# PSU.net
KiCad netlist of a schematic drawn in Altium Designer
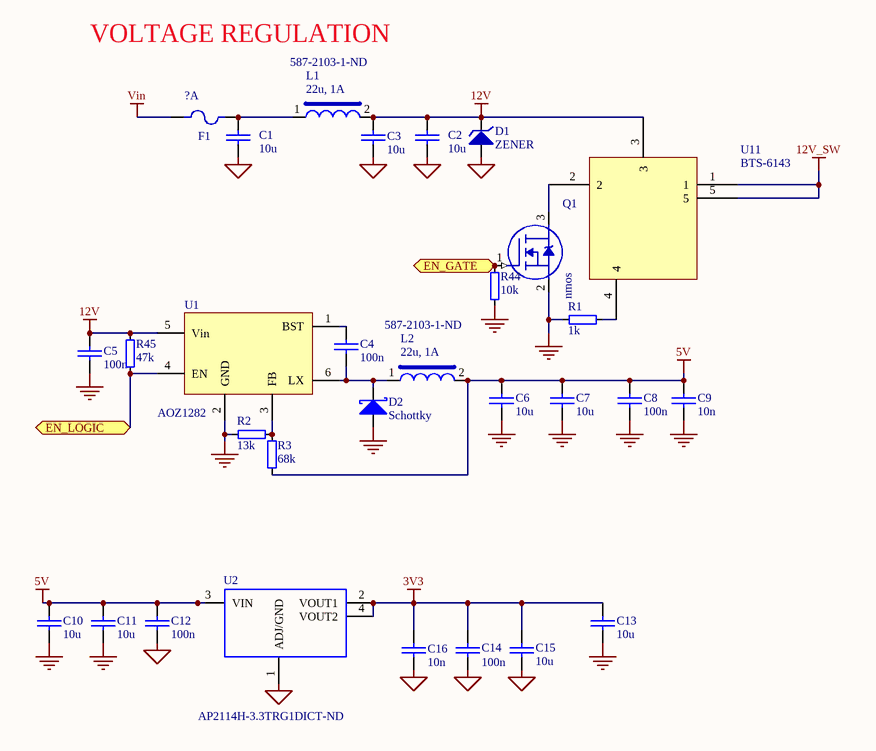
[diagram p0: PSU.SchDoc]

(export (version "E")
  (design (tool "Eeschema 10.0.6"))
  (components
    (comp (ref "C1")
      (value "10u")
      (footprint "0805")
      (description "Capacitor")
      (libsource (lib "Schematic Library") (part "CAPACITOR"))
    )
    (comp (ref "C2")
      (value "10u")
      (footprint "0805")
      (description "Capacitor")
      (libsource (lib "Schematic Library") (part "CAPACITOR"))
    )
    (comp (ref "C3")
      (value "10u")
      (footprint "0805")
      (description "Capacitor")
      (libsource (lib "Schematic Library") (part "CAPACITOR"))
    )
    (comp (ref "C4")
      (value "100n")
      (footprint "0603")
      (fields (field (name "DIGIKEY PART NUMBER") "PCC2153CT-ND"))
      (libsource (lib "*") (part "CAP"))
    )
    (comp (ref "C5")
      (value "100n")
      (footprint "0603")
      (fields (field (name "DIGIKEY PART NUMBER") "PCC2153CT-ND"))
      (libsource (lib "*") (part "CAP"))
    )
    (comp (ref "C6")
      (value "10u")
      (footprint "0805")
      (description "Capacitor")
      (libsource (lib "Schematic Library") (part "CAP"))
    )
    (comp (ref "C7")
      (value "10u")
      (footprint "0805")
      (description "Capacitor")
      (libsource (lib "Schematic Library") (part "CAP"))
    )
    (comp (ref "C8")
      (value "100n")
      (footprint "0603")
      (fields (field (name "DIGIKEY PART NUMBER") "PCC2153CT-ND"))
      (libsource (lib "*") (part "CAP"))
    )
    (comp (ref "C9")
      (value "10n")
      (footprint "0603")
      (fields (field (name "DIGIKEY PART NUMBER") "PCC2153CT-ND"))
      (libsource (lib "*") (part "CAP"))
    )
    (comp (ref "C10")
      (value "10u")
      (footprint "0805")
      (description "Capacitor")
      (libsource (lib "Schematic Library") (part "CAP"))
    )
    (comp (ref "C11")
      (value "10u")
      (footprint "0805")
      (description "Capacitor")
      (libsource (lib "Schematic Library") (part "CAP"))
    )
    (comp (ref "C12")
      (value "100n")
      (footprint "0603")
      (description "Capacitor")
      (libsource (lib "Schematic Library") (part "CAPACITOR"))
    )
    (comp (ref "C13")
      (value "10u")
      (footprint "0805")
      (description "Capacitor")
      (libsource (lib "Schematic Library") (part "CAP"))
    )
    (comp (ref "C14")
      (value "100n")
      (footprint "0603")
      (fields (field (name "DIGIKEY PART NUMBER") "490-4775-1-ND"))
      (libsource (lib "*") (part "CAP"))
    )
    (comp (ref "C15")
      (value "10u")
      (footprint "0805")
      (description "Capacitor")
      (libsource (lib "Schematic Library") (part "CAPACITOR"))
    )
    (comp (ref "C16")
      (value "10n")
      (footprint "0603")
      (fields (field (name "DIGIKEY PART NUMBER") "PCC2153CT-ND"))
      (libsource (lib "*") (part "CAP"))
    )
    (comp (ref "D1")
      (value "ZENER")
      (footprint "DO214AC")
      (description "Zener Diode")
      (libsource (lib "Schematic Library") (part "ZENER"))
    )
    (comp (ref "D2")
      (value "Schottky")
      (footprint "DO214AC")
      (description "Schottky Diode")
      (fields (field (name "DIGIKEY PART NUMBER") "SD103AWSTPMSCT-ND"))
      (libsource (lib "Schematic Library") (part "DIODE SCHOTTKY"))
    )
    (comp (ref "F1")
      (value "?A")
      (footprint "1206")
      (description "Thermal Fuse")
      (libsource (lib "Schematic Library") (part "FUSE"))
    )
    (comp (ref "L1")
      (value "22u, 1A")
      (footprint "2220")
      (description "Standard single coil inductor")
      (fields (field (name "SUPPLIER PART NUMBER 1") "587-2103-1-ND"))
      (libsource (lib "Schematic Library") (part "INDUCTOR-1 COIL"))
    )
    (comp (ref "L2")
      (value "22u, 1A")
      (footprint "2220")
      (description "Standard single coil inductor")
      (fields (field (name "SUPPLIER PART NUMBER 1") "587-2103-1-ND"))
      (libsource (lib "Schematic Library") (part "INDUCTOR-1 COIL"))
    )
    (comp (ref "Q1")
      (value "nmos")
      (footprint "SOT23")
      (description "N-Channel MOSFET")
      (libsource (lib "Schematic Library") (part "MOSFET-N"))
    )
    (comp (ref "R1")
      (value "1k")
      (footprint "0603")
      (description "Resistor")
      (libsource (lib "Schematic Library") (part "RESISTOR"))
    )
    (comp (ref "R2")
      (value "13k")
      (footprint "0603")
      (description "Resistor")
      (libsource (lib "Schematic Library") (part "RESISTOR"))
    )
    (comp (ref "R3")
      (value "68k")
      (footprint "0603")
      (description "Resistor")
      (libsource (lib "Schematic Library") (part "RESISTOR"))
    )
    (comp (ref "R44") (value "10k") (footprint "0603") (libsource (lib "*") (part "RES4")))
    (comp (ref "R45")
      (value "47k")
      (footprint "0805")
      (description "Resistor")
      (libsource (lib "Schematic Library") (part "RESISTOR"))
    )
    (comp (ref "U1")
      (value "AOZ1282")
      (footprint "SOT23-6")
      (fields (field (name "DIGIKEY PART NUMBER") "785-1613-1-ND"))
      (libsource (lib "Schematic Library") (part "AOZ1280"))
    )
    (comp (ref "U2")
      (value "AP2114H-3.3TRG1DICT-ND")
      (footprint "SOT223")
      (libsource (lib "Schematic Library") (part "TLV1117-33"))
    )
    (comp (ref "U11")
      (value "BTS-6143")
      (footprint "TO252-5-11")
      (libsource (lib "zytek_ctl") (part "BTS-6143"))
    )
  )
  (nets
    (net (code "1") (name "/EN_GATE") (class "Default")
      (node (ref "Q1") (pin "1") (pinfunction "G_1") (pintype "input"))
      (node (ref "R44") (pin "1") (pintype "passive"))
    )
    (net (code "2") (name "/EN_LOGIC") (class "Default")
      (node (ref "R45") (pin "2") (pintype "passive"))
      (node (ref "U1") (pin "4") (pinfunction "EN_4") (pintype "passive"))
    )
    (net (code "3") (name "3V3") (class "Default")
      (node (ref "C13") (pin "2") (pinfunction "2_2") (pintype "passive"))
      (node (ref "C14") (pin "1") (pinfunction "1_1") (pintype "passive"))
      (node (ref "C15") (pin "1") (pinfunction "1_1") (pintype "passive"))
      (node (ref "C16") (pin "1") (pinfunction "1_1") (pintype "passive"))
      (node (ref "U2") (pin "2") (pinfunction "VOUT1_2") (pintype "passive"))
      (node (ref "U2") (pin "4") (pinfunction "VOUT2_4") (pintype "passive"))
    )
    (net (code "4") (name "5V") (class "Default")
      (node (ref "C10") (pin "2") (pinfunction "2_2") (pintype "passive"))
      (node (ref "C11") (pin "2") (pinfunction "2_2") (pintype "passive"))
      (node (ref "C12") (pin "1") (pinfunction "1_1") (pintype "passive"))
      (node (ref "C6") (pin "2") (pinfunction "2_2") (pintype "passive"))
      (node (ref "C7") (pin "2") (pinfunction "2_2") (pintype "passive"))
      (node (ref "C8") (pin "1") (pinfunction "1_1") (pintype "passive"))
      (node (ref "C9") (pin "1") (pinfunction "1_1") (pintype "passive"))
      (node (ref "L2") (pin "2") (pinfunction "2_2") (pintype "passive"))
      (node (ref "R3") (pin "1") (pintype "passive"))
      (node (ref "U2") (pin "3") (pinfunction "VIN_3") (pintype "passive"))
    )
    (net (code "5") (name "12V") (class "Default")
      (node (ref "C2") (pin "1") (pinfunction "1_1") (pintype "passive"))
      (node (ref "C3") (pin "1") (pinfunction "1_1") (pintype "passive"))
      (node (ref "C5") (pin "1") (pinfunction "1_1") (pintype "passive"))
      (node (ref "D1") (pin "K") (pinfunction "K_K") (pintype "passive"))
      (node (ref "L1") (pin "2") (pinfunction "2_2") (pintype "passive"))
      (node (ref "R45") (pin "1") (pintype "passive"))
      (node (ref "U1") (pin "5") (pinfunction "Vin_5") (pintype "passive"))
      (node (ref "U11") (pin "3") (pinfunction "3_3") (pintype "passive"))
    )
    (net (code "6") (name "12V_SW") (class "Default")
      (node (ref "U11") (pin "1") (pinfunction "1_1") (pintype "passive"))
      (node (ref "U11") (pin "5") (pinfunction "5_5") (pintype "passive"))
    )
    (net (code "7") (name "GND") (class "Default")
      (node (ref "C1") (pin "2") (pinfunction "2_2") (pintype "passive"))
      (node (ref "C10") (pin "1") (pinfunction "1_1") (pintype "passive"))
      (node (ref "C11") (pin "1") (pinfunction "1_1") (pintype "passive"))
      (node (ref "C12") (pin "2") (pinfunction "2_2") (pintype "passive"))
      (node (ref "C13") (pin "1") (pinfunction "1_1") (pintype "passive"))
      (node (ref "C14") (pin "2") (pinfunction "2_2") (pintype "passive"))
      (node (ref "C15") (pin "2") (pinfunction "2_2") (pintype "passive"))
      (node (ref "C16") (pin "2") (pinfunction "2_2") (pintype "passive"))
      (node (ref "C2") (pin "2") (pinfunction "2_2") (pintype "passive"))
      (node (ref "C3") (pin "2") (pinfunction "2_2") (pintype "passive"))
      (node (ref "C5") (pin "2") (pinfunction "2_2") (pintype "passive"))
      (node (ref "C6") (pin "1") (pinfunction "1_1") (pintype "passive"))
      (node (ref "C7") (pin "1") (pinfunction "1_1") (pintype "passive"))
      (node (ref "C8") (pin "2") (pinfunction "2_2") (pintype "passive"))
      (node (ref "C9") (pin "2") (pinfunction "2_2") (pintype "passive"))
      (node (ref "D1") (pin "A") (pinfunction "A_A") (pintype "passive"))
      (node (ref "D2") (pin "A") (pinfunction "A_A") (pintype "passive"))
      (node (ref "Q1") (pin "2") (pinfunction "S_2") (pintype "passive"))
      (node (ref "R1") (pin "1") (pintype "passive"))
      (node (ref "R2") (pin "1") (pintype "passive"))
      (node (ref "R44") (pin "2") (pintype "passive"))
      (node (ref "U1") (pin "2") (pinfunction "GND_2") (pintype "passive"))
      (node (ref "U2") (pin "1") (pinfunction "ADJ/GND_1") (pintype "passive"))
    )
    (net (code "8") (name "Net-(C1-Pad1)") (class "Default")
      (node (ref "C1") (pin "1") (pinfunction "1_1") (pintype "passive"))
      (node (ref "F1") (pin "2") (pinfunction "2_2") (pintype "passive"))
      (node (ref "L1") (pin "1") (pinfunction "1_1") (pintype "passive"))
    )
    (net (code "9") (name "Net-(Q1-D)") (class "Default")
      (node (ref "Q1") (pin "3") (pinfunction "D_3") (pintype "passive"))
      (node (ref "U11") (pin "2") (pinfunction "2_2") (pintype "passive"))
    )
    (net (code "10") (name "Net-(R1-Pad2)") (class "Default")
      (node (ref "R1") (pin "2") (pintype "passive"))
      (node (ref "U11") (pin "4") (pinfunction "4_4") (pintype "passive"))
    )
    (net (code "11") (name "Net-(U1-BST)") (class "Default")
      (node (ref "C4") (pin "2") (pinfunction "2_2") (pintype "passive"))
      (node (ref "U1") (pin "1") (pinfunction "BST_1") (pintype "passive"))
    )
    (net (code "12") (name "Net-(U1-FB)") (class "Default")
      (node (ref "R2") (pin "2") (pintype "passive"))
      (node (ref "R3") (pin "2") (pintype "passive"))
      (node (ref "U1") (pin "3") (pinfunction "FB_3") (pintype "passive"))
    )
    (net (code "13") (name "Net-(U1-LX)") (class "Default")
      (node (ref "C4") (pin "1") (pinfunction "1_1") (pintype "passive"))
      (node (ref "D2") (pin "K") (pinfunction "K_K") (pintype "passive"))
      (node (ref "L2") (pin "1") (pinfunction "1_1") (pintype "passive"))
      (node (ref "U1") (pin "6") (pinfunction "LX_6") (pintype "passive"))
    )
    (net (code "14") (name "Vin") (class "Default")
      (node (ref "F1") (pin "1") (pinfunction "1_1") (pintype "passive"))
    )
  )
)
